# frontpanel_prototype.net
KiCad netlist of a schematic drawn in EAGLE
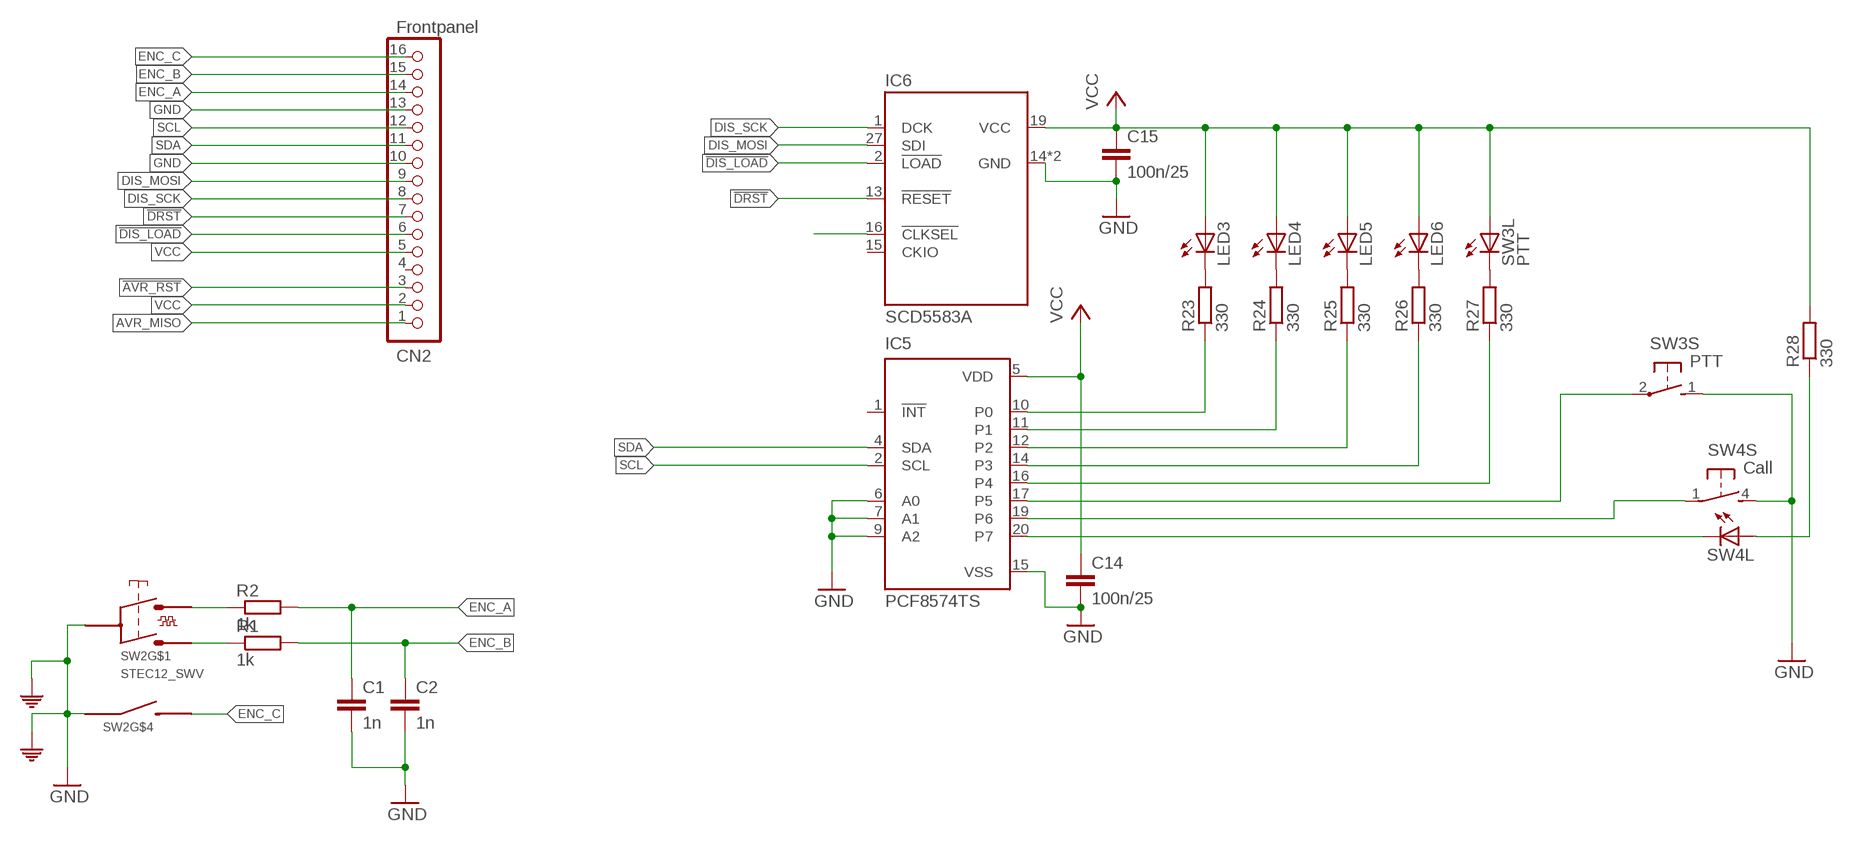
[diagram p0: schematic, sheet 1]

(export (version "E")
  (design (tool "Eeschema 10.0.6"))
  (components
    (comp (ref "C1")
      (value "1n")
      (footprint "eagle-import:C0603")
      (libsource (lib "eagle-import") (part "C-EUC0603"))
    )
    (comp (ref "C2")
      (value "1n")
      (footprint "eagle-import:C0603")
      (libsource (lib "eagle-import") (part "C-EUC0603"))
    )
    (comp (ref "C14")
      (value "100n/25")
      (footprint "eagle-import:C0603")
      (libsource (lib "eagle-import") (part "C-EUC0603"))
    )
    (comp (ref "C15")
      (value "100n/25")
      (footprint "eagle-import:C0603")
      (libsource (lib "eagle-import") (part "C-EUC0603"))
    )
    (comp (ref "CN2")
      (value "Frontpanel")
      (footprint "eagle-import:MOLEX-505278-1633")
      (libsource (lib "eagle-import") (part "MOLEX-505278-1633"))
    )
    (comp (ref "IC5")
      (value "PCF8574TS")
      (footprint "eagle-import:SSOP20")
      (libsource (lib "eagle-import") (part "PCF8574TS"))
    )
    (comp (ref "IC6")
      (value "SCD5583A")
      (footprint "eagle-import:SCD558XA")
      (libsource (lib "eagle-import") (part "SCD5583A"))
    )
    (comp (ref "LED3")
      (value "LEDLZR181")
      (footprint "eagle-import:LZR181")
      (libsource (lib "eagle-import") (part "LEDLZR181"))
    )
    (comp (ref "LED4")
      (value "LEDLZR181")
      (footprint "eagle-import:LZR181")
      (libsource (lib "eagle-import") (part "LEDLZR181"))
    )
    (comp (ref "LED5")
      (value "LEDLZR181")
      (footprint "eagle-import:LZR181")
      (libsource (lib "eagle-import") (part "LEDLZR181"))
    )
    (comp (ref "LED6")
      (value "LEDLZR181")
      (footprint "eagle-import:LZR181")
      (libsource (lib "eagle-import") (part "LEDLZR181"))
    )
    (comp (ref "R1")
      (value "1k")
      (footprint "eagle-import:R0603")
      (libsource (lib "eagle-import") (part "R-EU_R0603"))
    )
    (comp (ref "R2")
      (value "1k")
      (footprint "eagle-import:R0603")
      (libsource (lib "eagle-import") (part "R-EU_R0603"))
    )
    (comp (ref "R23")
      (value "330")
      (footprint "eagle-import:R0603")
      (libsource (lib "eagle-import") (part "R-EU_R0603"))
    )
    (comp (ref "R24")
      (value "330")
      (footprint "eagle-import:R0603")
      (libsource (lib "eagle-import") (part "R-EU_R0603"))
    )
    (comp (ref "R25")
      (value "330")
      (footprint "eagle-import:R0603")
      (libsource (lib "eagle-import") (part "R-EU_R0603"))
    )
    (comp (ref "R26")
      (value "330")
      (footprint "eagle-import:R0603")
      (libsource (lib "eagle-import") (part "R-EU_R0603"))
    )
    (comp (ref "R27")
      (value "330")
      (footprint "eagle-import:R0603")
      (libsource (lib "eagle-import") (part "R-EU_R0603"))
    )
    (comp (ref "R28")
      (value "330")
      (footprint "eagle-import:R0603")
      (libsource (lib "eagle-import") (part "R-EU_R0603"))
    )
    (comp (ref "SW2")
      (value "STEC12_SWV")
      (footprint "eagle-import:STEC12_VERT")
      (libsource (lib "eagle-import") (part "STEC12_SWV"))
    )
    (comp (ref "SW3")
      (value "PTT")
      (footprint "eagle-import:6425")
      (libsource (lib "eagle-import") (part "6425-0101"))
    )
    (comp (ref "SW4")
      (value "Call")
      (footprint "eagle-import:MEC_5G_LED")
      (libsource (lib "eagle-import") (part "5GSH9_LED"))
    )
  )
  (nets
    (net (code "1") (name "/~{AVR_RST}") (class "Default")
      (node (ref "CN2") (pin "3") (pinfunction "3_3") (pintype "bidirectional"))
    )
    (net (code "2") (name "/~{DIS_LOAD}") (class "Default")
      (node (ref "CN2") (pin "6") (pinfunction "6_6") (pintype "bidirectional"))
      (node (ref "IC6") (pin "2") (pinfunction "~{LOAD}_2") (pintype "bidirectional"))
    )
    (net (code "3") (name "/~{DRST}") (class "Default")
      (node (ref "CN2") (pin "7") (pinfunction "7_7") (pintype "bidirectional"))
      (node (ref "IC6") (pin "13") (pinfunction "~{RESET}_13") (pintype "bidirectional"))
    )
    (net (code "4") (name "AVR_MISO") (class "Default")
      (node (ref "CN2") (pin "1") (pinfunction "1_1") (pintype "bidirectional"))
    )
    (net (code "5") (name "DIS_MOSI") (class "Default")
      (node (ref "CN2") (pin "9") (pinfunction "9_9") (pintype "bidirectional"))
      (node (ref "IC6") (pin "27") (pinfunction "SDI_27") (pintype "bidirectional"))
    )
    (net (code "6") (name "DIS_SCK") (class "Default")
      (node (ref "CN2") (pin "8") (pinfunction "8_8") (pintype "bidirectional"))
      (node (ref "IC6") (pin "1") (pinfunction "DCK_1") (pintype "bidirectional"))
    )
    (net (code "7") (name "ENC_A") (class "Default")
      (node (ref "C1") (pin "1") (pinfunction "1_1") (pintype "passive"))
      (node (ref "CN2") (pin "14") (pinfunction "14_14") (pintype "bidirectional"))
      (node (ref "R2") (pin "2") (pinfunction "2_2") (pintype "passive"))
    )
    (net (code "8") (name "ENC_B") (class "Default")
      (node (ref "C2") (pin "1") (pinfunction "1_1") (pintype "passive"))
      (node (ref "CN2") (pin "15") (pinfunction "15_15") (pintype "bidirectional"))
      (node (ref "R1") (pin "2") (pinfunction "2_2") (pintype "passive"))
    )
    (net (code "9") (name "ENC_C") (class "Default")
      (node (ref "CN2") (pin "16") (pinfunction "16_16") (pintype "bidirectional"))
      (node (ref "SW2") (pin "Y") (pinfunction "P$2_Y") (pintype "bidirectional"))
    )
    (net (code "10") (name "GND") (class "Default")
      (node (ref "C1") (pin "2") (pinfunction "2_2") (pintype "passive"))
      (node (ref "C14") (pin "2") (pinfunction "2_2") (pintype "passive"))
      (node (ref "C15") (pin "2") (pinfunction "2_2") (pintype "passive"))
      (node (ref "C2") (pin "2") (pinfunction "2_2") (pintype "passive"))
      (node (ref "CN2") (pin "10") (pinfunction "10_10") (pintype "bidirectional"))
      (node (ref "CN2") (pin "13") (pinfunction "13_13") (pintype "bidirectional"))
      (node (ref "IC5") (pin "15") (pinfunction "VSS_15") (pintype "power_in"))
      (node (ref "IC5") (pin "6") (pinfunction "A0_6") (pintype "input"))
      (node (ref "IC5") (pin "7") (pinfunction "A1_7") (pintype "input"))
      (node (ref "IC5") (pin "9") (pinfunction "A2_9") (pintype "input"))
      (node (ref "IC6") (pin "14") (pinfunction "GND_14") (pintype "power_in"))
      (node (ref "IC6") (pin "28") (pinfunction "GND_28") (pintype "power_in"))
      (node (ref "SW2") (pin "B") (pinfunction "B_B") (pintype "bidirectional"))
      (node (ref "SW2") (pin "G1") (pinfunction "P$1_G1") (pintype "bidirectional"))
      (node (ref "SW2") (pin "G2") (pinfunction "P$1_G2") (pintype "bidirectional"))
      (node (ref "SW2") (pin "X") (pinfunction "P$1_X") (pintype "bidirectional"))
      (node (ref "SW3") (pin "1") (pinfunction "S_1") (pintype "passive"))
      (node (ref "SW4") (pin "4") (pinfunction "S_4") (pintype "passive"))
    )
    (net (code "11") (name "Net-(IC5-P0)") (class "Default")
      (node (ref "IC5") (pin "10") (pinfunction "P0_10") (pintype "bidirectional"))
      (node (ref "R23") (pin "1") (pinfunction "1_1") (pintype "passive"))
    )
    (net (code "12") (name "Net-(IC5-P1)") (class "Default")
      (node (ref "IC5") (pin "11") (pinfunction "P1_11") (pintype "bidirectional"))
      (node (ref "R24") (pin "1") (pinfunction "1_1") (pintype "passive"))
    )
    (net (code "13") (name "Net-(IC5-P2)") (class "Default")
      (node (ref "IC5") (pin "12") (pinfunction "P2_12") (pintype "bidirectional"))
      (node (ref "R25") (pin "1") (pinfunction "1_1") (pintype "passive"))
    )
    (net (code "14") (name "Net-(IC5-P3)") (class "Default")
      (node (ref "IC5") (pin "14") (pinfunction "P3_14") (pintype "bidirectional"))
      (node (ref "R26") (pin "1") (pinfunction "1_1") (pintype "passive"))
    )
    (net (code "15") (name "Net-(IC5-P4)") (class "Default")
      (node (ref "IC5") (pin "16") (pinfunction "P4_16") (pintype "bidirectional"))
      (node (ref "R27") (pin "1") (pinfunction "1_1") (pintype "passive"))
    )
    (net (code "16") (name "Net-(IC5-P5)") (class "Default")
      (node (ref "IC5") (pin "17") (pinfunction "P5_17") (pintype "bidirectional"))
      (node (ref "SW3") (pin "2") (pinfunction "P_2") (pintype "passive"))
    )
    (net (code "17") (name "Net-(IC5-P6)") (class "Default")
      (node (ref "IC5") (pin "19") (pinfunction "P6_19") (pintype "bidirectional"))
      (node (ref "SW4") (pin "1") (pinfunction "P_1") (pintype "passive"))
    )
    (net (code "18") (name "Net-(IC5-P7)") (class "Default")
      (node (ref "IC5") (pin "20") (pinfunction "P7_20") (pintype "bidirectional"))
      (node (ref "SW4") (pin "2") (pinfunction "C_2") (pintype "passive"))
    )
    (net (code "19") (name "Net-(LED3-C)") (class "Default")
      (node (ref "LED3") (pin "K") (pinfunction "C_K") (pintype "passive"))
      (node (ref "R23") (pin "2") (pinfunction "2_2") (pintype "passive"))
    )
    (net (code "20") (name "Net-(LED4-C)") (class "Default")
      (node (ref "LED4") (pin "K") (pinfunction "C_K") (pintype "passive"))
      (node (ref "R24") (pin "2") (pinfunction "2_2") (pintype "passive"))
    )
    (net (code "21") (name "Net-(LED5-C)") (class "Default")
      (node (ref "LED5") (pin "K") (pinfunction "C_K") (pintype "passive"))
      (node (ref "R25") (pin "2") (pinfunction "2_2") (pintype "passive"))
    )
    (net (code "22") (name "Net-(LED6-C)") (class "Default")
      (node (ref "LED6") (pin "K") (pinfunction "C_K") (pintype "passive"))
      (node (ref "R26") (pin "2") (pinfunction "2_2") (pintype "passive"))
    )
    (net (code "23") (name "Net-(R1-Pad1)") (class "Default")
      (node (ref "R1") (pin "1") (pinfunction "1_1") (pintype "passive"))
      (node (ref "SW2") (pin "C") (pinfunction "C_C") (pintype "bidirectional"))
    )
    (net (code "24") (name "Net-(R2-Pad1)") (class "Default")
      (node (ref "R2") (pin "1") (pinfunction "1_1") (pintype "passive"))
      (node (ref "SW2") (pin "A") (pinfunction "A_A") (pintype "bidirectional"))
    )
    (net (code "25") (name "Net-(SW3A-C)") (class "Default")
      (node (ref "R27") (pin "2") (pinfunction "2_2") (pintype "passive"))
      (node (ref "SW3") (pin "K") (pinfunction "C_K") (pintype "passive"))
    )
    (net (code "26") (name "Net-(SW4A-A)") (class "Default")
      (node (ref "R28") (pin "1") (pinfunction "1_1") (pintype "passive"))
      (node (ref "SW4") (pin "3") (pinfunction "A_3") (pintype "passive"))
    )
    (net (code "27") (name "SCL") (class "Default")
      (node (ref "CN2") (pin "12") (pinfunction "12_12") (pintype "bidirectional"))
      (node (ref "IC5") (pin "2") (pinfunction "SCL_2") (pintype "input"))
    )
    (net (code "28") (name "SDA") (class "Default")
      (node (ref "CN2") (pin "11") (pinfunction "11_11") (pintype "bidirectional"))
      (node (ref "IC5") (pin "4") (pinfunction "SDA_4") (pintype "bidirectional"))
    )
    (net (code "29") (name "VCC") (class "Default")
      (node (ref "C14") (pin "1") (pinfunction "1_1") (pintype "passive"))
      (node (ref "C15") (pin "1") (pinfunction "1_1") (pintype "passive"))
      (node (ref "CN2") (pin "2") (pinfunction "2_2") (pintype "bidirectional"))
      (node (ref "CN2") (pin "5") (pinfunction "5_5") (pintype "bidirectional"))
      (node (ref "IC5") (pin "5") (pinfunction "VDD_5") (pintype "power_in"))
      (node (ref "IC6") (pin "19") (pinfunction "VCC_19") (pintype "power_in"))
      (node (ref "LED3") (pin "A") (pinfunction "A_A") (pintype "passive"))
      (node (ref "LED4") (pin "A") (pinfunction "A_A") (pintype "passive"))
      (node (ref "LED5") (pin "A") (pinfunction "A_A") (pintype "passive"))
      (node (ref "LED6") (pin "A") (pinfunction "A_A") (pintype "passive"))
      (node (ref "R28") (pin "2") (pinfunction "2_2") (pintype "passive"))
      (node (ref "SW3") (pin "A") (pinfunction "A_A") (pintype "passive"))
    )
    (net (code "30") (name "unconnected-(CN2-Pad4)") (class "Default")
      (node (ref "CN2") (pin "4") (pinfunction "4_4") (pintype "bidirectional"))
    )
    (net (code "31") (name "unconnected-(IC5-~{INT}-Pad1)") (class "Default")
      (node (ref "IC5") (pin "1") (pinfunction "~{INT}_1") (pintype "output"))
    )
    (net (code "32") (name "unconnected-(IC6-CKIO-Pad15)") (class "Default")
      (node (ref "IC6") (pin "15") (pinfunction "CKIO_15") (pintype "bidirectional"))
    )
    (net (code "33") (name "unconnected-(IC6-~{CLKSEL}-Pad16)") (class "Default")
      (node (ref "IC6") (pin "16") (pinfunction "~{CLKSEL}_16") (pintype "bidirectional"))
    )
  )
)
